# ARDUINO.net
KiCad netlist of a schematic drawn in Altium Designer
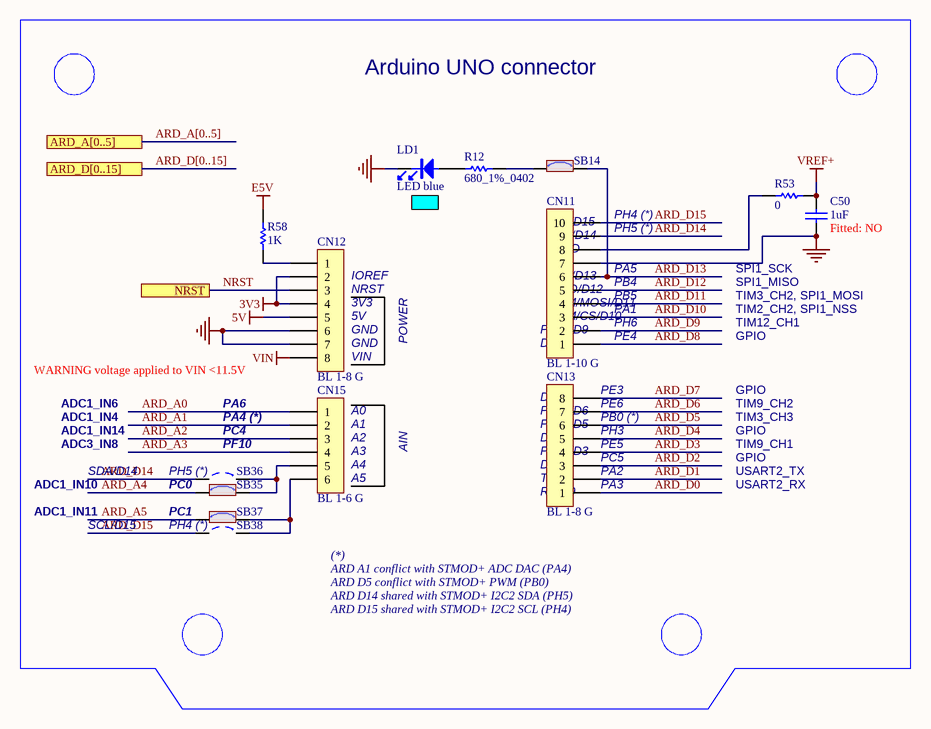
[diagram p0: ARDUINO.SchDoc]

(export (version "E")
  (design (tool "Eeschema 10.0.6"))
  (components
    (comp (ref "C50")
      (value "1uF")
      (footprint "0603C")
      (description "Capacitor,1uF,16V,X5R,10%,0603,YAGEO")
      (fields (field (name "FITTED") "NO"))
      (libsource (lib "MCD_TOOLS_CAPACITOR") (part "Cap_1uF_X5R_10%_0603"))
    )
    (comp (ref "CN11")
      (value "BL 1-10 G")
      (footprint "HDR_1X10_2R54_W")
      (description "Header, 10-Pin, Single row, female, THT, 2.54")
      (libsource (lib "MCD_TOOLS_CONNECTOR") (part "Header 10X1_Female_THT"))
    )
    (comp (ref "CN12")
      (value "BL 1-8 G")
      (footprint "HDR_1X8_2R54_W")
      (description "Header, 8-Pins, Single row, female, THT, 2.54")
      (libsource (lib "MCD_TOOLS_CONNECTOR") (part "Header 8X1_Female_THT"))
    )
    (comp (ref "CN13")
      (value "BL 1-8 G")
      (footprint "HDR_1X8_2R54_W")
      (description "Header, 8-Pins, Single row, female, THT, 2.54")
      (libsource (lib "") (part "Header 8X1_Female_THT_1"))
    )
    (comp (ref "CN15")
      (value "BL 1-6 G")
      (footprint "HDR_1X6_2R54_W")
      (description "Header, 6-Pins, Single row, female THT, 2.54")
      (libsource (lib "MCD_TOOLS_CONNECTOR") (part "Header 6X1_Female_THT"))
    )
    (comp (ref "LD1")
      (value "LED blue")
      (footprint "0603D")
      (description "LED blue 0603")
      (libsource (lib "MCD_TEMP_NPA") (part "LED_blue"))
    )
    (comp (ref "R12")
      (value "680_1%_0402")
      (footprint "0402R")
      (description "Resistor,680,0402,1%,YAGEO")
      (libsource (lib "MCD_TEMP_NPA") (part "Res_680_1%_0402"))
    )
    (comp (ref "R53")
      (value "0")
      (footprint "0402R")
      (description "Resistor,0,0402,5%,YAGEO")
      (libsource (lib "MCD_TOOLS") (part "Res_0_5%_0402"))
    )
    (comp (ref "R58")
      (value "1K")
      (footprint "0402R")
      (description "Resistor,1K,0402,1%,YAGEO")
      (libsource (lib "MCD_TOOLS_RESISTOR") (part "Res_1K_1%_0402"))
    )
    (comp (ref "SB14")
      (value "Solder Bridge ON")
      (footprint "JP2_SMD")
      (libsource (lib "MCD_TOOLS") (part "SB_ON"))
    )
    (comp (ref "SB35")
      (value "Solder Bridge ON")
      (footprint "JP2_SMD")
      (libsource (lib "MCD_TOOLS") (part "SB_ON"))
    )
    (comp (ref "SB36")
      (value "Solder Bridge OFF")
      (footprint "JP2_SMD")
      (libsource (lib "MCD_TOOLS") (part "SB_OFF"))
    )
    (comp (ref "SB37")
      (value "Solder Bridge ON")
      (footprint "JP2_SMD")
      (libsource (lib "MCD_TOOLS") (part "SB_ON"))
    )
    (comp (ref "SB38")
      (value "Solder Bridge OFF")
      (footprint "JP2_SMD")
      (libsource (lib "MCD_TOOLS") (part "SB_OFF"))
    )
  )
  (nets
    (net (code "1") (name "/ARD_A0") (class "Default")
      (node (ref "CN15") (pin "1") (pinfunction "1_1") (pintype "passive"))
    )
    (net (code "2") (name "/ARD_A1") (class "Default")
      (node (ref "CN15") (pin "2") (pinfunction "2_2") (pintype "passive"))
    )
    (net (code "3") (name "/ARD_A2") (class "Default")
      (node (ref "CN15") (pin "3") (pinfunction "3_3") (pintype "passive"))
    )
    (net (code "4") (name "/ARD_A3") (class "Default")
      (node (ref "CN15") (pin "4") (pinfunction "4_4") (pintype "passive"))
    )
    (net (code "5") (name "/ARD_A4") (class "Default")
      (node (ref "SB35") (pin "1") (pinfunction "1_1") (pintype "passive"))
    )
    (net (code "6") (name "/ARD_A5") (class "Default")
      (node (ref "SB37") (pin "1") (pinfunction "1_1") (pintype "passive"))
    )
    (net (code "8") (name "/ARD_D0") (class "Default")
      (node (ref "CN13") (pin "1") (pinfunction "1_1") (pintype "passive"))
    )
    (net (code "9") (name "/ARD_D1") (class "Default")
      (node (ref "CN13") (pin "2") (pinfunction "2_2") (pintype "passive"))
    )
    (net (code "10") (name "/ARD_D2") (class "Default")
      (node (ref "CN13") (pin "3") (pinfunction "3_3") (pintype "passive"))
    )
    (net (code "11") (name "/ARD_D3") (class "Default")
      (node (ref "CN13") (pin "4") (pinfunction "4_4") (pintype "passive"))
    )
    (net (code "12") (name "/ARD_D4") (class "Default")
      (node (ref "CN13") (pin "5") (pinfunction "5_5") (pintype "passive"))
    )
    (net (code "13") (name "/ARD_D5") (class "Default")
      (node (ref "CN13") (pin "6") (pinfunction "6_6") (pintype "passive"))
    )
    (net (code "14") (name "/ARD_D6") (class "Default")
      (node (ref "CN13") (pin "7") (pinfunction "7_7") (pintype "passive"))
    )
    (net (code "15") (name "/ARD_D7") (class "Default")
      (node (ref "CN13") (pin "8") (pinfunction "8_8") (pintype "passive"))
    )
    (net (code "16") (name "/ARD_D8") (class "Default")
      (node (ref "CN11") (pin "1") (pinfunction "1_1") (pintype "passive"))
    )
    (net (code "17") (name "/ARD_D9") (class "Default")
      (node (ref "CN11") (pin "2") (pinfunction "2_2") (pintype "passive"))
    )
    (net (code "18") (name "/ARD_D10") (class "Default")
      (node (ref "CN11") (pin "3") (pinfunction "3_3") (pintype "passive"))
    )
    (net (code "19") (name "/ARD_D11") (class "Default")
      (node (ref "CN11") (pin "4") (pinfunction "4_4") (pintype "passive"))
    )
    (net (code "20") (name "/ARD_D12") (class "Default")
      (node (ref "CN11") (pin "5") (pinfunction "5_5") (pintype "passive"))
    )
    (net (code "21") (name "/ARD_D13") (class "Default")
      (node (ref "CN11") (pin "6") (pinfunction "6_6") (pintype "passive"))
      (node (ref "SB14") (pin "2") (pinfunction "2_2") (pintype "passive"))
    )
    (net (code "22") (name "/ARD_D14") (class "Default")
      (node (ref "CN11") (pin "9") (pinfunction "9_9") (pintype "passive"))
      (node (ref "SB36") (pin "1") (pinfunction "1_1") (pintype "passive"))
    )
    (net (code "23") (name "/ARD_D15") (class "Default")
      (node (ref "CN11") (pin "10") (pinfunction "10_10") (pintype "passive"))
      (node (ref "SB38") (pin "1") (pinfunction "1_1") (pintype "passive"))
    )
    (net (code "25") (name "/NRST") (class "Default")
      (node (ref "CN12") (pin "3") (pinfunction "3_3") (pintype "passive"))
    )
    (net (code "26") (name "3V3") (class "Default")
      (node (ref "CN12") (pin "2") (pinfunction "2_2") (pintype "passive"))
      (node (ref "CN12") (pin "4") (pinfunction "4_4") (pintype "passive"))
    )
    (net (code "27") (name "5V") (class "Default")
      (node (ref "CN12") (pin "5") (pinfunction "5_5") (pintype "passive"))
    )
    (net (code "28") (name "E5V") (class "Default")
      (node (ref "R58") (pin "2") (pinfunction "2_2") (pintype "passive"))
    )
    (net (code "29") (name "GND") (class "Default")
      (node (ref "C50") (pin "1") (pinfunction "1_1") (pintype "passive"))
      (node (ref "CN11") (pin "7") (pinfunction "7_7") (pintype "passive"))
      (node (ref "CN12") (pin "6") (pinfunction "6_6") (pintype "passive"))
      (node (ref "CN12") (pin "7") (pinfunction "7_7") (pintype "passive"))
      (node (ref "LD1") (pin "2") (pintype "passive"))
    )
    (net (code "30") (name "Net-(CN11-Pad8)") (class "Default")
      (node (ref "CN11") (pin "8") (pinfunction "8_8") (pintype "passive"))
      (node (ref "R53") (pin "1") (pinfunction "1_1") (pintype "passive"))
    )
    (net (code "31") (name "Net-(CN12-Pad1)") (class "Default")
      (node (ref "CN12") (pin "1") (pinfunction "1_1") (pintype "passive"))
      (node (ref "R58") (pin "1") (pinfunction "1_1") (pintype "passive"))
    )
    (net (code "32") (name "Net-(CN15-Pad5)") (class "Default")
      (node (ref "CN15") (pin "5") (pinfunction "5_5") (pintype "passive"))
      (node (ref "SB35") (pin "2") (pinfunction "2_2") (pintype "passive"))
      (node (ref "SB36") (pin "2") (pinfunction "2_2") (pintype "passive"))
    )
    (net (code "33") (name "Net-(CN15-Pad6)") (class "Default")
      (node (ref "CN15") (pin "6") (pinfunction "6_6") (pintype "passive"))
      (node (ref "SB37") (pin "2") (pinfunction "2_2") (pintype "passive"))
      (node (ref "SB38") (pin "2") (pinfunction "2_2") (pintype "passive"))
    )
    (net (code "34") (name "Net-(LD1-Pad1)") (class "Default")
      (node (ref "LD1") (pin "1") (pintype "passive"))
      (node (ref "R12") (pin "1") (pinfunction "1_1") (pintype "passive"))
    )
    (net (code "35") (name "Net-(R12-Pad2)") (class "Default")
      (node (ref "R12") (pin "2") (pinfunction "2_2") (pintype "passive"))
      (node (ref "SB14") (pin "1") (pinfunction "1_1") (pintype "passive"))
    )
    (net (code "36") (name "VIN") (class "Default")
      (node (ref "CN12") (pin "8") (pinfunction "8_8") (pintype "passive"))
    )
    (net (code "37") (name "VREF+") (class "Default")
      (node (ref "C50") (pin "2") (pinfunction "2_2") (pintype "passive"))
      (node (ref "R53") (pin "2") (pinfunction "2_2") (pintype "passive"))
    )
  )
)
